# AIWAC_A33_RGB5_LCD__20190109.net
KiCad netlist of a schematic drawn in Altium Designer
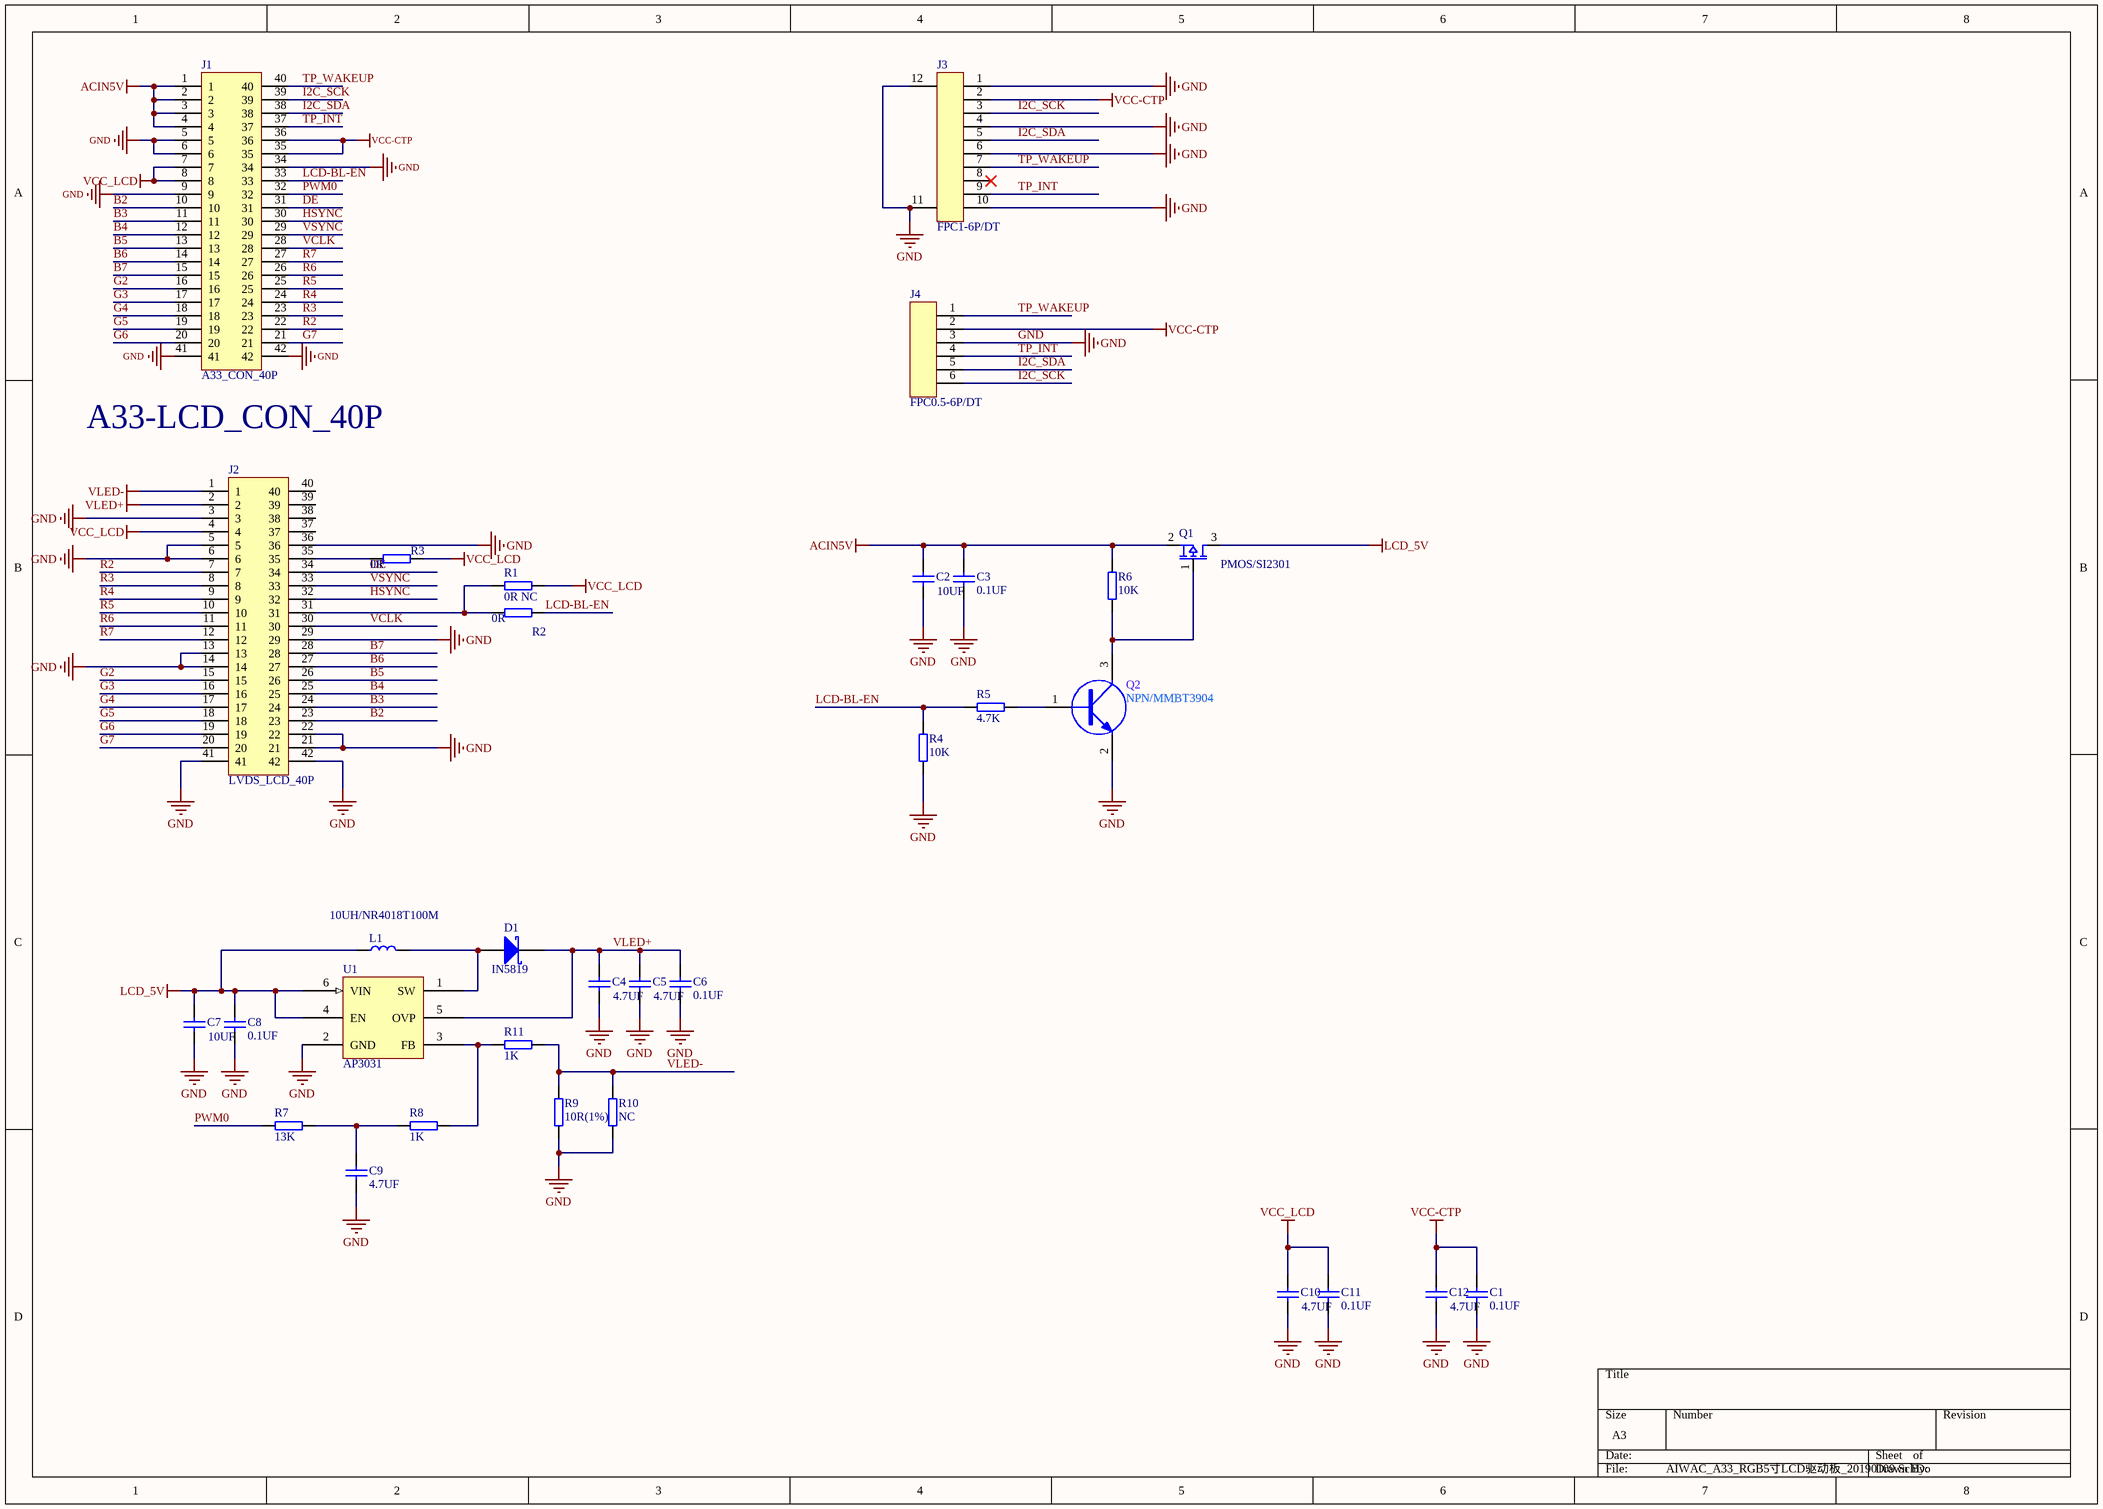
[diagram p0: AIWAC_A33_RGB5寸LCD驱动板_20190109.SchDoc]

(export (version "E")
  (design (tool "Eeschema 10.0.6"))
  (components
    (comp (ref "C1")
      (value "0.1UF")
      (footprint "C0402")
      (description "贴片电容-陶瓷")
      (libsource (lib "Capacitor") (part "C0402X7R-104J10V"))
    )
    (comp (ref "C2")
      (value "10UF")
      (footprint "C0805")
      (description "贴片电容-陶瓷")
      (libsource (lib "Capacitor") (part "C0805X7R-226K25V"))
    )
    (comp (ref "C3")
      (value "0.1UF")
      (footprint "C0402")
      (description "贴片电容-陶瓷")
      (libsource (lib "Capacitor") (part "C0402X7R-104J10V"))
    )
    (comp (ref "C4")
      (value "4.7UF")
      (footprint "C0805")
      (description "贴片电容-陶瓷")
      (libsource (lib "Capacitor") (part "C0805X7R-226K25V"))
    )
    (comp (ref "C5")
      (value "4.7UF")
      (footprint "C0805")
      (description "贴片电容-陶瓷")
      (libsource (lib "Capacitor") (part "C0805X7R-226K25V"))
    )
    (comp (ref "C6")
      (value "0.1UF")
      (footprint "C0402")
      (description "贴片电容-陶瓷")
      (libsource (lib "Capacitor") (part "C0402X7R-104J10V"))
    )
    (comp (ref "C7")
      (value "10UF")
      (footprint "C0805")
      (description "贴片电容-陶瓷")
      (libsource (lib "Capacitor") (part "C0805X7R-226K25V"))
    )
    (comp (ref "C8")
      (value "0.1UF")
      (footprint "C0402")
      (description "贴片电容-陶瓷")
      (libsource (lib "Capacitor") (part "C0402X7R-104J10V"))
    )
    (comp (ref "C9")
      (value "4.7UF")
      (footprint "C0603")
      (description "贴片电容-陶瓷")
      (libsource (lib "Capacitor") (part "C0603X7R-330J25V"))
    )
    (comp (ref "C10")
      (value "4.7UF")
      (footprint "C0805")
      (description "贴片电容-陶瓷")
      (libsource (lib "Capacitor") (part "C0805X7R-226K25V"))
    )
    (comp (ref "C11")
      (value "0.1UF")
      (footprint "C0402")
      (description "贴片电容-陶瓷")
      (libsource (lib "Capacitor") (part "C0402X7R-104J10V"))
    )
    (comp (ref "C12")
      (value "4.7UF")
      (footprint "C0805")
      (description "贴片电容-陶瓷")
      (libsource (lib "Capacitor") (part "C0805X7R-226K25V"))
    )
    (comp (ref "D1")
      (value "IN5819")
      (footprint "D1206")
      (description "Schottky Diode")
      (fields (field (name "PUBLISHER") "Altium Limited"))
      (libsource (lib "XU-GENARAL SCH") (part "D Schottky"))
    )
    (comp (ref "J1")
      (value "A33_CON_40P")
      (footprint "LCD P40")
      (description "LCD_40P")
      (libsource (lib "Connector") (part "LCD_40P"))
    )
    (comp (ref "J2")
      (value "LVDS_LCD_40P")
      (footprint "FPC-59240HU010R")
      (description "LCD_40P")
      (libsource (lib "Connector") (part "LCD_40P"))
    )
    (comp (ref "J3")
      (value "FPC1-6P/DT")
      (footprint "FPC0.5-10P/下接")
      (description "FPC端子")
      (libsource (lib "AIWAC_A33_LVDS07_Project") (part "J-FPC0.5-10P/DT"))
    )
    (comp (ref "J4")
      (value "FPC0.5-6P/DT")
      (footprint "FPC0.5-6P/下接")
      (description "FPC端子")
      (libsource (lib "Sheye-Connector") (part "J-FPC0.5-6P/DT"))
    )
    (comp (ref "L1")
      (value "10UH/NR4018T100M")
      (footprint "D1206")
      (description "贴片电感-屏蔽")
      (libsource (lib "AIWAC-bolsterV01") (part "3.3uH"))
    )
    (comp (ref "Q1")
      (value "PMOS/SI2301")
      (footprint "U-SOT-23-3")
      (description "贴片MOSFET管")
      (libsource (lib "AIWAC-bolsterV01") (part "PMOS"))
    )
    (comp (ref "Q2")
      (value "NPN/MMBT3904")
      (footprint "U-SOT-23-3")
      (description "三极管")
      (libsource (lib "标准通用原理图库") (part "SS8050 TO-23"))
    )
    (comp (ref "R1")
      (value "0R NC")
      (footprint "0402")
      (description "贴片电阻-通用")
      (libsource (lib "Resistor") (part "R0603-10KF"))
    )
    (comp (ref "R2")
      (value "0R")
      (footprint "0402")
      (description "贴片电阻-通用")
      (libsource (lib "Resistor") (part "R0603-10KF"))
    )
    (comp (ref "R3")
      (value "0R")
      (footprint "0402")
      (description "贴片电阻-通用")
      (libsource (lib "Resistor") (part "R0603-10KF"))
    )
    (comp (ref "R4")
      (value "10K")
      (footprint "0402")
      (description "贴片电阻-通用")
      (libsource (lib "Resistor") (part "R0603-10KF"))
    )
    (comp (ref "R5")
      (value "4.7K")
      (footprint "0402")
      (description "贴片电阻-通用")
      (libsource (lib "Resistor") (part "R0603-10KF"))
    )
    (comp (ref "R6")
      (value "10K")
      (footprint "0402")
      (description "贴片电阻-通用")
      (libsource (lib "Resistor") (part "R0603-10KF"))
    )
    (comp (ref "R7")
      (value "13K")
      (footprint "0402")
      (description "贴片电阻-通用")
      (libsource (lib "Resistor") (part "R0603-10KF"))
    )
    (comp (ref "R8")
      (value "1K")
      (footprint "0402")
      (description "贴片电阻-通用")
      (libsource (lib "Resistor") (part "R0603-10KF"))
    )
    (comp (ref "R9")
      (value "10R(1%)")
      (footprint "0402")
      (description "贴片电阻-通用")
      (libsource (lib "Resistor") (part "R0603-10KF"))
    )
    (comp (ref "R10")
      (value "NC")
      (footprint "0402")
      (description "贴片电阻-通用")
      (libsource (lib "Resistor") (part "R0603-10KF"))
    )
    (comp (ref "R11")
      (value "1K")
      (footprint "0402")
      (description "贴片电阻-通用")
      (libsource (lib "Resistor") (part "R0603-10KF"))
    )
    (comp (ref "U1")
      (value "AP3031")
      (footprint "U-SOT-23-6")
      (libsource (lib "AIWAC-bolsterV01") (part "AP3031"))
    )
  )
  (nets
    (net (code "1") (name "/B2") (class "Default")
      (node (ref "J1") (pin "10") (pinfunction "10_10") (pintype "passive"))
      (node (ref "J2") (pin "23") (pinfunction "23_23") (pintype "passive"))
    )
    (net (code "2") (name "/B3") (class "Default")
      (node (ref "J1") (pin "11") (pinfunction "11_11") (pintype "passive"))
      (node (ref "J2") (pin "24") (pinfunction "24_24") (pintype "passive"))
    )
    (net (code "3") (name "/B4") (class "Default")
      (node (ref "J1") (pin "12") (pinfunction "12_12") (pintype "passive"))
      (node (ref "J2") (pin "25") (pinfunction "25_25") (pintype "passive"))
    )
    (net (code "4") (name "/B5") (class "Default")
      (node (ref "J1") (pin "13") (pinfunction "13_13") (pintype "passive"))
      (node (ref "J2") (pin "26") (pinfunction "26_26") (pintype "passive"))
    )
    (net (code "5") (name "/B6") (class "Default")
      (node (ref "J1") (pin "14") (pinfunction "14_14") (pintype "passive"))
      (node (ref "J2") (pin "27") (pinfunction "27_27") (pintype "passive"))
    )
    (net (code "6") (name "/B7") (class "Default")
      (node (ref "J1") (pin "15") (pinfunction "15_15") (pintype "passive"))
      (node (ref "J2") (pin "28") (pinfunction "28_28") (pintype "passive"))
    )
    (net (code "7") (name "/DE") (class "Default")
      (node (ref "J1") (pin "31") (pinfunction "31_31") (pintype "passive"))
      (node (ref "J2") (pin "34") (pinfunction "34_34") (pintype "passive"))
    )
    (net (code "8") (name "/G2") (class "Default")
      (node (ref "J1") (pin "16") (pinfunction "16_16") (pintype "passive"))
      (node (ref "J2") (pin "15") (pinfunction "15_15") (pintype "passive"))
    )
    (net (code "9") (name "/G3") (class "Default")
      (node (ref "J1") (pin "17") (pinfunction "17_17") (pintype "passive"))
      (node (ref "J2") (pin "16") (pinfunction "16_16") (pintype "passive"))
    )
    (net (code "10") (name "/G4") (class "Default")
      (node (ref "J1") (pin "18") (pinfunction "18_18") (pintype "passive"))
      (node (ref "J2") (pin "17") (pinfunction "17_17") (pintype "passive"))
    )
    (net (code "11") (name "/G5") (class "Default")
      (node (ref "J1") (pin "19") (pinfunction "19_19") (pintype "passive"))
      (node (ref "J2") (pin "18") (pinfunction "18_18") (pintype "passive"))
    )
    (net (code "12") (name "/G6") (class "Default")
      (node (ref "J1") (pin "20") (pinfunction "20_20") (pintype "passive"))
      (node (ref "J2") (pin "19") (pinfunction "19_19") (pintype "passive"))
    )
    (net (code "13") (name "/G7") (class "Default")
      (node (ref "J1") (pin "21") (pinfunction "21_21") (pintype "passive"))
      (node (ref "J2") (pin "20") (pinfunction "20_20") (pintype "passive"))
    )
    (net (code "14") (name "/HSYNC") (class "Default")
      (node (ref "J1") (pin "30") (pinfunction "30_30") (pintype "passive"))
      (node (ref "J2") (pin "32") (pinfunction "32_32") (pintype "passive"))
    )
    (net (code "15") (name "/I2C_SCK") (class "Default")
      (node (ref "J1") (pin "39") (pinfunction "39_39") (pintype "passive"))
      (node (ref "J3") (pin "3") (pinfunction "3_3") (pintype "passive"))
      (node (ref "J4") (pin "6") (pinfunction "6_6") (pintype "passive"))
    )
    (net (code "16") (name "/I2C_SDA") (class "Default")
      (node (ref "J1") (pin "38") (pinfunction "38_38") (pintype "passive"))
      (node (ref "J3") (pin "5") (pinfunction "5_5") (pintype "passive"))
      (node (ref "J4") (pin "5") (pinfunction "5_5") (pintype "passive"))
    )
    (net (code "17") (name "/LCD-BL-EN") (class "Default")
      (node (ref "J1") (pin "33") (pinfunction "33_33") (pintype "passive"))
      (node (ref "R2") (pin "1") (pinfunction "1_1") (pintype "passive"))
      (node (ref "R4") (pin "1") (pinfunction "1_1") (pintype "passive"))
      (node (ref "R5") (pin "2") (pinfunction "2_2") (pintype "passive"))
    )
    (net (code "18") (name "/PWM0") (class "Default")
      (node (ref "J1") (pin "32") (pinfunction "32_32") (pintype "passive"))
      (node (ref "R7") (pin "2") (pinfunction "2_2") (pintype "passive"))
    )
    (net (code "19") (name "/R2") (class "Default")
      (node (ref "J1") (pin "22") (pinfunction "22_22") (pintype "passive"))
      (node (ref "J2") (pin "7") (pinfunction "7_7") (pintype "passive"))
    )
    (net (code "20") (name "/R3") (class "Default")
      (node (ref "J1") (pin "23") (pinfunction "23_23") (pintype "passive"))
      (node (ref "J2") (pin "8") (pinfunction "8_8") (pintype "passive"))
    )
    (net (code "21") (name "/R4") (class "Default")
      (node (ref "J1") (pin "24") (pinfunction "24_24") (pintype "passive"))
      (node (ref "J2") (pin "9") (pinfunction "9_9") (pintype "passive"))
    )
    (net (code "22") (name "/R5") (class "Default")
      (node (ref "J1") (pin "25") (pinfunction "25_25") (pintype "passive"))
      (node (ref "J2") (pin "10") (pinfunction "10_10") (pintype "passive"))
    )
    (net (code "23") (name "/R6") (class "Default")
      (node (ref "J1") (pin "26") (pinfunction "26_26") (pintype "passive"))
      (node (ref "J2") (pin "11") (pinfunction "11_11") (pintype "passive"))
    )
    (net (code "24") (name "/R7") (class "Default")
      (node (ref "J1") (pin "27") (pinfunction "27_27") (pintype "passive"))
      (node (ref "J2") (pin "12") (pinfunction "12_12") (pintype "passive"))
    )
    (net (code "25") (name "/TP_INT") (class "Default")
      (node (ref "J1") (pin "37") (pinfunction "37_37") (pintype "passive"))
      (node (ref "J3") (pin "9") (pinfunction "6_9") (pintype "passive"))
      (node (ref "J4") (pin "4") (pinfunction "4_4") (pintype "passive"))
    )
    (net (code "26") (name "/TP_WAKEUP") (class "Default")
      (node (ref "J1") (pin "40") (pinfunction "40_40") (pintype "passive"))
      (node (ref "J3") (pin "7") (pinfunction "6_7") (pintype "passive"))
      (node (ref "J4") (pin "1") (pinfunction "1_1") (pintype "passive"))
    )
    (net (code "27") (name "/VCLK") (class "Default")
      (node (ref "J1") (pin "28") (pinfunction "28_28") (pintype "passive"))
      (node (ref "J2") (pin "30") (pinfunction "30_30") (pintype "passive"))
    )
    (net (code "28") (name "/VSYNC") (class "Default")
      (node (ref "J1") (pin "29") (pinfunction "29_29") (pintype "passive"))
      (node (ref "J2") (pin "33") (pinfunction "33_33") (pintype "passive"))
    )
    (net (code "29") (name "ACIN5V") (class "Default")
      (node (ref "C2") (pin "1") (pinfunction "1_1") (pintype "passive"))
      (node (ref "C3") (pin "1") (pinfunction "1_1") (pintype "passive"))
      (node (ref "J1") (pin "1") (pinfunction "1_1") (pintype "passive"))
      (node (ref "J1") (pin "2") (pinfunction "2_2") (pintype "passive"))
      (node (ref "J1") (pin "3") (pinfunction "3_3") (pintype "passive"))
      (node (ref "J1") (pin "4") (pinfunction "4_4") (pintype "passive"))
      (node (ref "Q1") (pin "2") (pinfunction "2_2") (pintype "passive"))
      (node (ref "R6") (pin "1") (pinfunction "1_1") (pintype "passive"))
    )
    (net (code "30") (name "GND") (class "Default")
      (node (ref "C1") (pin "2") (pinfunction "2_2") (pintype "passive"))
      (node (ref "C10") (pin "2") (pinfunction "2_2") (pintype "passive"))
      (node (ref "C11") (pin "2") (pinfunction "2_2") (pintype "passive"))
      (node (ref "C12") (pin "2") (pinfunction "2_2") (pintype "passive"))
      (node (ref "C2") (pin "2") (pinfunction "2_2") (pintype "passive"))
      (node (ref "C3") (pin "2") (pinfunction "2_2") (pintype "passive"))
      (node (ref "C4") (pin "2") (pinfunction "2_2") (pintype "passive"))
      (node (ref "C5") (pin "2") (pinfunction "2_2") (pintype "passive"))
      (node (ref "C6") (pin "2") (pinfunction "2_2") (pintype "passive"))
      (node (ref "C7") (pin "2") (pinfunction "2_2") (pintype "passive"))
      (node (ref "C8") (pin "2") (pinfunction "2_2") (pintype "passive"))
      (node (ref "C9") (pin "1") (pinfunction "1_1") (pintype "passive"))
      (node (ref "J1") (pin "34") (pinfunction "34_34") (pintype "passive"))
      (node (ref "J1") (pin "41") (pinfunction "41_41") (pintype "passive"))
      (node (ref "J1") (pin "42") (pinfunction "42_42") (pintype "passive"))
      (node (ref "J1") (pin "5") (pinfunction "5_5") (pintype "passive"))
      (node (ref "J1") (pin "6") (pinfunction "6_6") (pintype "passive"))
      (node (ref "J1") (pin "9") (pinfunction "9_9") (pintype "passive"))
      (node (ref "J2") (pin "13") (pinfunction "13_13") (pintype "passive"))
      (node (ref "J2") (pin "14") (pinfunction "14_14") (pintype "passive"))
      (node (ref "J2") (pin "21") (pinfunction "21_21") (pintype "passive"))
      (node (ref "J2") (pin "22") (pinfunction "22_22") (pintype "passive"))
      (node (ref "J2") (pin "29") (pinfunction "29_29") (pintype "passive"))
      (node (ref "J2") (pin "3") (pinfunction "3_3") (pintype "passive"))
      (node (ref "J2") (pin "36") (pinfunction "36_36") (pintype "passive"))
      (node (ref "J2") (pin "41") (pinfunction "41_41") (pintype "passive"))
      (node (ref "J2") (pin "42") (pinfunction "42_42") (pintype "passive"))
      (node (ref "J2") (pin "5") (pinfunction "5_5") (pintype "passive"))
      (node (ref "J2") (pin "6") (pinfunction "6_6") (pintype "passive"))
      (node (ref "J3") (pin "1") (pinfunction "1_1") (pintype "passive"))
      (node (ref "J3") (pin "10") (pinfunction "6_10") (pintype "passive"))
      (node (ref "J3") (pin "11") (pinfunction "6_11") (pintype "passive"))
      (node (ref "J3") (pin "12") (pinfunction "6_12") (pintype "passive"))
      (node (ref "J3") (pin "4") (pinfunction "4_4") (pintype "passive"))
      (node (ref "J3") (pin "6") (pinfunction "6_6") (pintype "passive"))
      (node (ref "J4") (pin "3") (pinfunction "3_3") (pintype "passive"))
      (node (ref "Q2") (pin "2") (pinfunction "E_2") (pintype "passive"))
      (node (ref "R10") (pin "2") (pinfunction "2_2") (pintype "passive"))
      (node (ref "R4") (pin "2") (pinfunction "2_2") (pintype "passive"))
      (node (ref "R9") (pin "2") (pinfunction "2_2") (pintype "passive"))
      (node (ref "U1") (pin "2") (pinfunction "GND_2") (pintype "power_in"))
    )
    (net (code "31") (name "LCD_5V") (class "Default")
      (node (ref "C7") (pin "1") (pinfunction "1_1") (pintype "passive"))
      (node (ref "C8") (pin "1") (pinfunction "1_1") (pintype "passive"))
      (node (ref "L1") (pin "1") (pinfunction "1_1") (pintype "passive"))
      (node (ref "Q1") (pin "3") (pinfunction "3_3") (pintype "passive"))
      (node (ref "U1") (pin "4") (pinfunction "EN_4") (pintype "passive"))
      (node (ref "U1") (pin "6") (pinfunction "VIN_6") (pintype "input"))
    )
    (net (code "32") (name "Net-(C9-Pad2)") (class "Default")
      (node (ref "C9") (pin "2") (pinfunction "2_2") (pintype "passive"))
      (node (ref "R7") (pin "1") (pinfunction "1_1") (pintype "passive"))
      (node (ref "R8") (pin "2") (pinfunction "2_2") (pintype "passive"))
    )
    (net (code "33") (name "Net-(D1-A)") (class "Default")
      (node (ref "D1") (pin "1") (pinfunction "A_1") (pintype "passive"))
      (node (ref "L1") (pin "2") (pinfunction "2_2") (pintype "passive"))
      (node (ref "U1") (pin "1") (pinfunction "SW_1") (pintype "passive"))
    )
    (net (code "34") (name "Net-(J2-Pad31)") (class "Default")
      (node (ref "J2") (pin "31") (pinfunction "31_31") (pintype "passive"))
      (node (ref "R1") (pin "2") (pinfunction "2_2") (pintype "passive"))
      (node (ref "R2") (pin "2") (pinfunction "2_2") (pintype "passive"))
    )
    (net (code "35") (name "Net-(J2-Pad35)") (class "Default")
      (node (ref "J2") (pin "35") (pinfunction "35_35") (pintype "passive"))
      (node (ref "R3") (pin "2") (pinfunction "2_2") (pintype "passive"))
    )
    (net (code "36") (name "Net-(Q2-B)") (class "Default")
      (node (ref "Q2") (pin "1") (pinfunction "B_1") (pintype "passive"))
      (node (ref "R5") (pin "1") (pinfunction "1_1") (pintype "passive"))
    )
    (net (code "37") (name "Net-(Q2-C)") (class "Default")
      (node (ref "Q1") (pin "1") (pinfunction "1_1") (pintype "passive"))
      (node (ref "Q2") (pin "3") (pinfunction "C_3") (pintype "passive"))
      (node (ref "R6") (pin "2") (pinfunction "2_2") (pintype "passive"))
    )
    (net (code "38") (name "Net-(U1-FB)") (class "Default")
      (node (ref "R11") (pin "2") (pinfunction "2_2") (pintype "passive"))
      (node (ref "R8") (pin "1") (pinfunction "1_1") (pintype "passive"))
      (node (ref "U1") (pin "3") (pinfunction "FB_3") (pintype "passive"))
    )
    (net (code "39") (name "VCC-CTP") (class "Default")
      (node (ref "C1") (pin "1") (pinfunction "1_1") (pintype "passive"))
      (node (ref "C12") (pin "1") (pinfunction "1_1") (pintype "passive"))
      (node (ref "J1") (pin "35") (pinfunction "35_35") (pintype "passive"))
      (node (ref "J1") (pin "36") (pinfunction "36_36") (pintype "passive"))
      (node (ref "J3") (pin "2") (pinfunction "2_2") (pintype "passive"))
      (node (ref "J4") (pin "2") (pinfunction "2_2") (pintype "passive"))
    )
    (net (code "40") (name "VCC_LCD") (class "Default")
      (node (ref "C10") (pin "1") (pinfunction "1_1") (pintype "passive"))
      (node (ref "C11") (pin "1") (pinfunction "1_1") (pintype "passive"))
      (node (ref "J1") (pin "7") (pinfunction "7_7") (pintype "passive"))
      (node (ref "J1") (pin "8") (pinfunction "8_8") (pintype "passive"))
      (node (ref "J2") (pin "4") (pinfunction "4_4") (pintype "passive"))
      (node (ref "R1") (pin "1") (pinfunction "1_1") (pintype "passive"))
      (node (ref "R3") (pin "1") (pinfunction "1_1") (pintype "passive"))
    )
    (net (code "41") (name "VLED+") (class "Default")
      (node (ref "C4") (pin "1") (pinfunction "1_1") (pintype "passive"))
      (node (ref "C5") (pin "1") (pinfunction "1_1") (pintype "passive"))
      (node (ref "C6") (pin "1") (pinfunction "1_1") (pintype "passive"))
      (node (ref "D1") (pin "2") (pinfunction "K_2") (pintype "passive"))
      (node (ref "J2") (pin "2") (pinfunction "2_2") (pintype "passive"))
      (node (ref "U1") (pin "5") (pinfunction "OVP_5") (pintype "passive"))
    )
    (net (code "42") (name "VLED-") (class "Default")
      (node (ref "J2") (pin "1") (pinfunction "1_1") (pintype "passive"))
      (node (ref "R10") (pin "1") (pinfunction "1_1") (pintype "passive"))
      (node (ref "R11") (pin "1") (pinfunction "1_1") (pintype "passive"))
      (node (ref "R9") (pin "1") (pinfunction "1_1") (pintype "passive"))
    )
    (net (code "43") (name "unconnected-(J2-Pad37)") (class "Default")
      (node (ref "J2") (pin "37") (pinfunction "37_37") (pintype "passive"))
    )
    (net (code "44") (name "unconnected-(J2-Pad38)") (class "Default")
      (node (ref "J2") (pin "38") (pinfunction "38_38") (pintype "passive"))
    )
    (net (code "45") (name "unconnected-(J2-Pad39)") (class "Default")
      (node (ref "J2") (pin "39") (pinfunction "39_39") (pintype "passive"))
    )
    (net (code "46") (name "unconnected-(J2-Pad40)") (class "Default")
      (node (ref "J2") (pin "40") (pinfunction "40_40") (pintype "passive"))
    )
    (net (code "47") (name "unconnected-(J3-6-Pad8)") (class "Default")
      (node (ref "J3") (pin "8") (pinfunction "6_8") (pintype "passive+no_connect"))
    )
  )
)
